# Input.net
KiCad netlist of a schematic drawn in Altium Designer
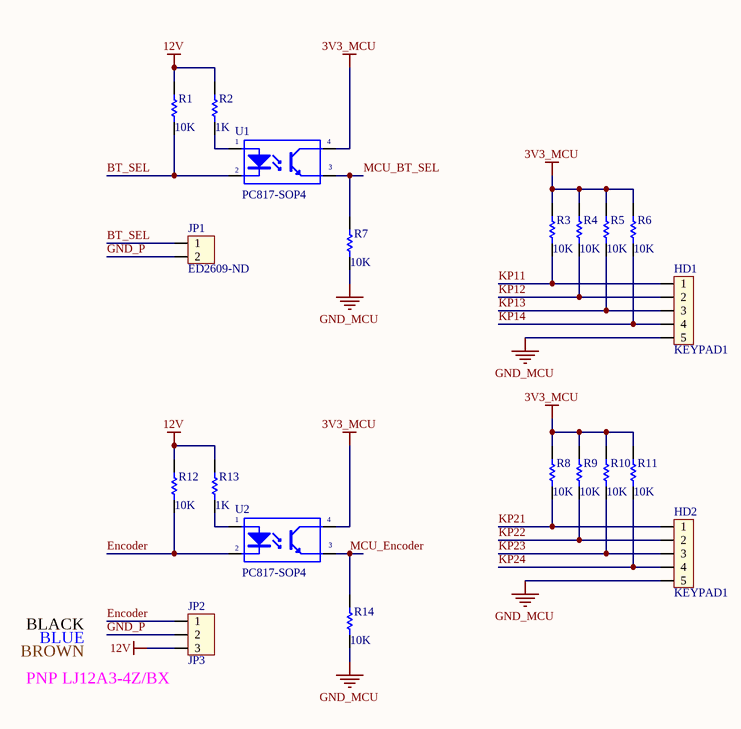
[diagram p0: Input.SchDoc]

(export (version "E")
  (design (tool "Eeschema 10.0.6"))
  (components
    (comp (ref "HD1")
      (value "KEYPAD1")
      (footprint "LPSON_CON:CON5")
      (description "Header 5")
      (fields (field (name "CREAT BY") "VanDungEvn@Gmail.com"))
      (libsource (lib "lpson") (part "Header5"))
    )
    (comp (ref "HD2")
      (value "KEYPAD1")
      (footprint "LPSON_CON:CON5")
      (description "Header 5")
      (fields (field (name "CREAT BY") "VanDungEvn@Gmail.com"))
      (libsource (lib "lpson") (part "Header5"))
    )
    (comp (ref "JP1")
      (value "ED2609-ND")
      (footprint "2EDGR-5.08-02P")
      (description "2 Position Wire to Board Terminal Block Horizontal with Board 0.200\" (5.08mm) Through Hole")
      (libsource (lib "lpson") (part "Con2"))
    )
    (comp (ref "JP2")
      (value "JP3")
      (footprint "2EDGR-5.08-03P")
      (description "Connector 3")
      (libsource (lib "lpson") (part "Con3"))
    )
    (comp (ref "R1")
      (value "10K")
      (footprint "Res 0805 SMD")
      (description "RES SMD 10K OHM 1% 1/10W 0603")
      (fields
        (field (name "MANUFACTURER") "Yageo")
        (field (name "MANUFACTURER PART NUMBER") "RC0603FR-0710KL")
      )
      (libsource (lib "GSHT_181013") (part "10K/R0603/1%"))
    )
    (comp (ref "R2")
      (value "1K")
      (footprint "Res 0805 SMD")
      (description "1 kOhms ±1% 0.125W, 1/8W Chip Resistor 0805 (2012 Metric) Automotive AEC-Q200 Thick Film")
      (libsource (lib "GSHT_181013") (part "10K/R0603/1%"))
    )
    (comp (ref "R3")
      (value "10K")
      (footprint "Res 0805 SMD")
      (description "RES SMD 249K OHM 1% 1/10W 0805")
      (fields
        (field (name "MANUFACTURER") "Yageo")
        (field (name "MANUFACTURER PART NUMBER") "RC0603FR-07249KL")
      )
      (libsource (lib "GSHT_181013") (part "249K/R0805/1%"))
    )
    (comp (ref "R4")
      (value "10K")
      (footprint "Res 0805 SMD")
      (description "RES SMD 249K OHM 1% 1/10W 0805")
      (fields
        (field (name "MANUFACTURER") "Yageo")
        (field (name "MANUFACTURER PART NUMBER") "RC0603FR-07249KL")
      )
      (libsource (lib "GSHT_181013") (part "249K/R0805/1%"))
    )
    (comp (ref "R5")
      (value "10K")
      (footprint "Res 0805 SMD")
      (description "RES SMD 249K OHM 1% 1/10W 0805")
      (fields
        (field (name "MANUFACTURER") "Yageo")
        (field (name "MANUFACTURER PART NUMBER") "RC0603FR-07249KL")
      )
      (libsource (lib "GSHT_181013") (part "249K/R0805/1%"))
    )
    (comp (ref "R6")
      (value "10K")
      (footprint "Res 0805 SMD")
      (description "RES SMD 249K OHM 1% 1/10W 0805")
      (fields
        (field (name "MANUFACTURER") "Yageo")
        (field (name "MANUFACTURER PART NUMBER") "RC0603FR-07249KL")
      )
      (libsource (lib "GSHT_181013") (part "249K/R0805/1%"))
    )
    (comp (ref "R7")
      (value "10K")
      (footprint "Res 0805 SMD")
      (description "RES SMD 249K OHM 1% 1/10W 0805")
      (fields
        (field (name "MANUFACTURER") "Yageo")
        (field (name "MANUFACTURER PART NUMBER") "RC0603FR-07249KL")
      )
      (libsource (lib "GSHT_181013") (part "249K/R0805/1%"))
    )
    (comp (ref "R8")
      (value "10K")
      (footprint "Res 0805 SMD")
      (description "RES SMD 249K OHM 1% 1/10W 0805")
      (fields
        (field (name "MANUFACTURER") "Yageo")
        (field (name "MANUFACTURER PART NUMBER") "RC0603FR-07249KL")
      )
      (libsource (lib "GSHT_181013") (part "249K/R0805/1%"))
    )
    (comp (ref "R9")
      (value "10K")
      (footprint "Res 0805 SMD")
      (description "RES SMD 249K OHM 1% 1/10W 0805")
      (fields
        (field (name "MANUFACTURER") "Yageo")
        (field (name "MANUFACTURER PART NUMBER") "RC0603FR-07249KL")
      )
      (libsource (lib "GSHT_181013") (part "249K/R0805/1%"))
    )
    (comp (ref "R10")
      (value "10K")
      (footprint "Res 0805 SMD")
      (description "RES SMD 249K OHM 1% 1/10W 0805")
      (fields
        (field (name "MANUFACTURER") "Yageo")
        (field (name "MANUFACTURER PART NUMBER") "RC0603FR-07249KL")
      )
      (libsource (lib "GSHT_181013") (part "249K/R0805/1%"))
    )
    (comp (ref "R11")
      (value "10K")
      (footprint "Res 0805 SMD")
      (description "RES SMD 249K OHM 1% 1/10W 0805")
      (fields
        (field (name "MANUFACTURER") "Yageo")
        (field (name "MANUFACTURER PART NUMBER") "RC0603FR-07249KL")
      )
      (libsource (lib "GSHT_181013") (part "249K/R0805/1%"))
    )
    (comp (ref "R12")
      (value "10K")
      (footprint "Res 0805 SMD")
      (description "RES SMD 10K OHM 1% 1/10W 0603")
      (fields
        (field (name "MANUFACTURER") "Yageo")
        (field (name "MANUFACTURER PART NUMBER") "RC0603FR-0710KL")
      )
      (libsource (lib "GSHT_181013") (part "10K/R0603/1%"))
    )
    (comp (ref "R13")
      (value "1K")
      (footprint "Res 0805 SMD")
      (description "1 kOhms ±1% 0.125W, 1/8W Chip Resistor 0805 (2012 Metric) Automotive AEC-Q200 Thick Film")
      (libsource (lib "GSHT_181013") (part "10K/R0603/1%"))
    )
    (comp (ref "R14")
      (value "10K")
      (footprint "Res 0805 SMD")
      (description "RES SMD 249K OHM 1% 1/10W 0805")
      (fields
        (field (name "MANUFACTURER") "Yageo")
        (field (name "MANUFACTURER PART NUMBER") "RC0603FR-07249KL")
      )
      (libsource (lib "GSHT_181013") (part "249K/R0805/1%"))
    )
    (comp (ref "U1")
      (value "PC817-SOP4")
      (footprint "TPC817-4SOP")
      (description "Optoisolator Transistor Output 5000Vrms 1 Channel 4-SOP")
      (libsource (lib "lpson") (part "PC817"))
    )
    (comp (ref "U2")
      (value "PC817-SOP4")
      (footprint "TPC817-4SOP")
      (description "Optoisolator Transistor Output 5000Vrms 1 Channel 4-SOP")
      (libsource (lib "lpson") (part "PC817"))
    )
  )
  (nets
    (net (code "1") (name "/BT_SEL") (class "Default")
      (node (ref "JP1") (pin "1") (pinfunction "1_1") (pintype "passive"))
      (node (ref "R1") (pin "1") (pinfunction "1_1") (pintype "passive"))
      (node (ref "U1") (pin "2") (pinfunction "K_2") (pintype "passive"))
    )
    (net (code "2") (name "/Encoder") (class "Default")
      (node (ref "JP2") (pin "1") (pinfunction "1_1") (pintype "passive"))
      (node (ref "R12") (pin "1") (pinfunction "1_1") (pintype "passive"))
      (node (ref "U2") (pin "2") (pinfunction "K_2") (pintype "passive"))
    )
    (net (code "3") (name "/GND_P") (class "Default")
      (node (ref "JP1") (pin "2") (pinfunction "2_2") (pintype "passive"))
      (node (ref "JP2") (pin "2") (pinfunction "2_2") (pintype "passive"))
    )
    (net (code "4") (name "/KP11") (class "Default")
      (node (ref "HD1") (pin "1") (pinfunction "1_1") (pintype "passive"))
      (node (ref "R3") (pin "1") (pinfunction "1_1") (pintype "passive"))
    )
    (net (code "5") (name "/KP12") (class "Default")
      (node (ref "HD1") (pin "2") (pinfunction "2_2") (pintype "passive"))
      (node (ref "R4") (pin "1") (pinfunction "1_1") (pintype "passive"))
    )
    (net (code "6") (name "/KP13") (class "Default")
      (node (ref "HD1") (pin "3") (pinfunction "3_3") (pintype "passive"))
      (node (ref "R5") (pin "1") (pinfunction "1_1") (pintype "passive"))
    )
    (net (code "7") (name "/KP14") (class "Default")
      (node (ref "HD1") (pin "4") (pinfunction "4_4") (pintype "passive"))
      (node (ref "R6") (pin "1") (pinfunction "1_1") (pintype "passive"))
    )
    (net (code "8") (name "/KP21") (class "Default")
      (node (ref "HD2") (pin "1") (pinfunction "1_1") (pintype "passive"))
      (node (ref "R8") (pin "1") (pinfunction "1_1") (pintype "passive"))
    )
    (net (code "9") (name "/KP22") (class "Default")
      (node (ref "HD2") (pin "2") (pinfunction "2_2") (pintype "passive"))
      (node (ref "R9") (pin "1") (pinfunction "1_1") (pintype "passive"))
    )
    (net (code "10") (name "/KP23") (class "Default")
      (node (ref "HD2") (pin "3") (pinfunction "3_3") (pintype "passive"))
      (node (ref "R10") (pin "1") (pinfunction "1_1") (pintype "passive"))
    )
    (net (code "11") (name "/KP24") (class "Default")
      (node (ref "HD2") (pin "4") (pinfunction "4_4") (pintype "passive"))
      (node (ref "R11") (pin "1") (pinfunction "1_1") (pintype "passive"))
    )
    (net (code "12") (name "/MCU_BT_SEL") (class "Default")
      (node (ref "R7") (pin "2") (pinfunction "2_2") (pintype "passive"))
      (node (ref "U1") (pin "3") (pinfunction "E_3") (pintype "passive"))
    )
    (net (code "13") (name "/MCU_Encoder") (class "Default")
      (node (ref "R14") (pin "2") (pinfunction "2_2") (pintype "passive"))
      (node (ref "U2") (pin "3") (pinfunction "E_3") (pintype "passive"))
    )
    (net (code "14") (name "3V3_MCU") (class "Default")
      (node (ref "R10") (pin "2") (pinfunction "2_2") (pintype "passive"))
      (node (ref "R11") (pin "2") (pinfunction "2_2") (pintype "passive"))
      (node (ref "R3") (pin "2") (pinfunction "2_2") (pintype "passive"))
      (node (ref "R4") (pin "2") (pinfunction "2_2") (pintype "passive"))
      (node (ref "R5") (pin "2") (pinfunction "2_2") (pintype "passive"))
      (node (ref "R6") (pin "2") (pinfunction "2_2") (pintype "passive"))
      (node (ref "R8") (pin "2") (pinfunction "2_2") (pintype "passive"))
      (node (ref "R9") (pin "2") (pinfunction "2_2") (pintype "passive"))
      (node (ref "U1") (pin "4") (pinfunction "C_4") (pintype "passive"))
      (node (ref "U2") (pin "4") (pinfunction "C_4") (pintype "passive"))
    )
    (net (code "15") (name "12V") (class "Default")
      (node (ref "JP2") (pin "3") (pinfunction "3_3") (pintype "passive"))
      (node (ref "R1") (pin "2") (pinfunction "2_2") (pintype "passive"))
      (node (ref "R12") (pin "2") (pinfunction "2_2") (pintype "passive"))
      (node (ref "R13") (pin "2") (pinfunction "2_2") (pintype "passive"))
      (node (ref "R2") (pin "2") (pinfunction "2_2") (pintype "passive"))
    )
    (net (code "16") (name "GND_MCU") (class "Default")
      (node (ref "HD1") (pin "5") (pinfunction "5_5") (pintype "passive"))
      (node (ref "HD2") (pin "5") (pinfunction "5_5") (pintype "passive"))
      (node (ref "R14") (pin "1") (pinfunction "1_1") (pintype "passive"))
      (node (ref "R7") (pin "1") (pinfunction "1_1") (pintype "passive"))
    )
    (net (code "17") (name "Net-(U1-A)") (class "Default")
      (node (ref "R2") (pin "1") (pinfunction "1_1") (pintype "passive"))
      (node (ref "U1") (pin "1") (pinfunction "A_1") (pintype "passive"))
    )
    (net (code "18") (name "Net-(U2-A)") (class "Default")
      (node (ref "R13") (pin "1") (pinfunction "1_1") (pintype "passive"))
      (node (ref "U2") (pin "1") (pinfunction "A_1") (pintype "passive"))
    )
  )
)
